# Regulation.net
KiCad netlist of a schematic drawn in Altium Designer
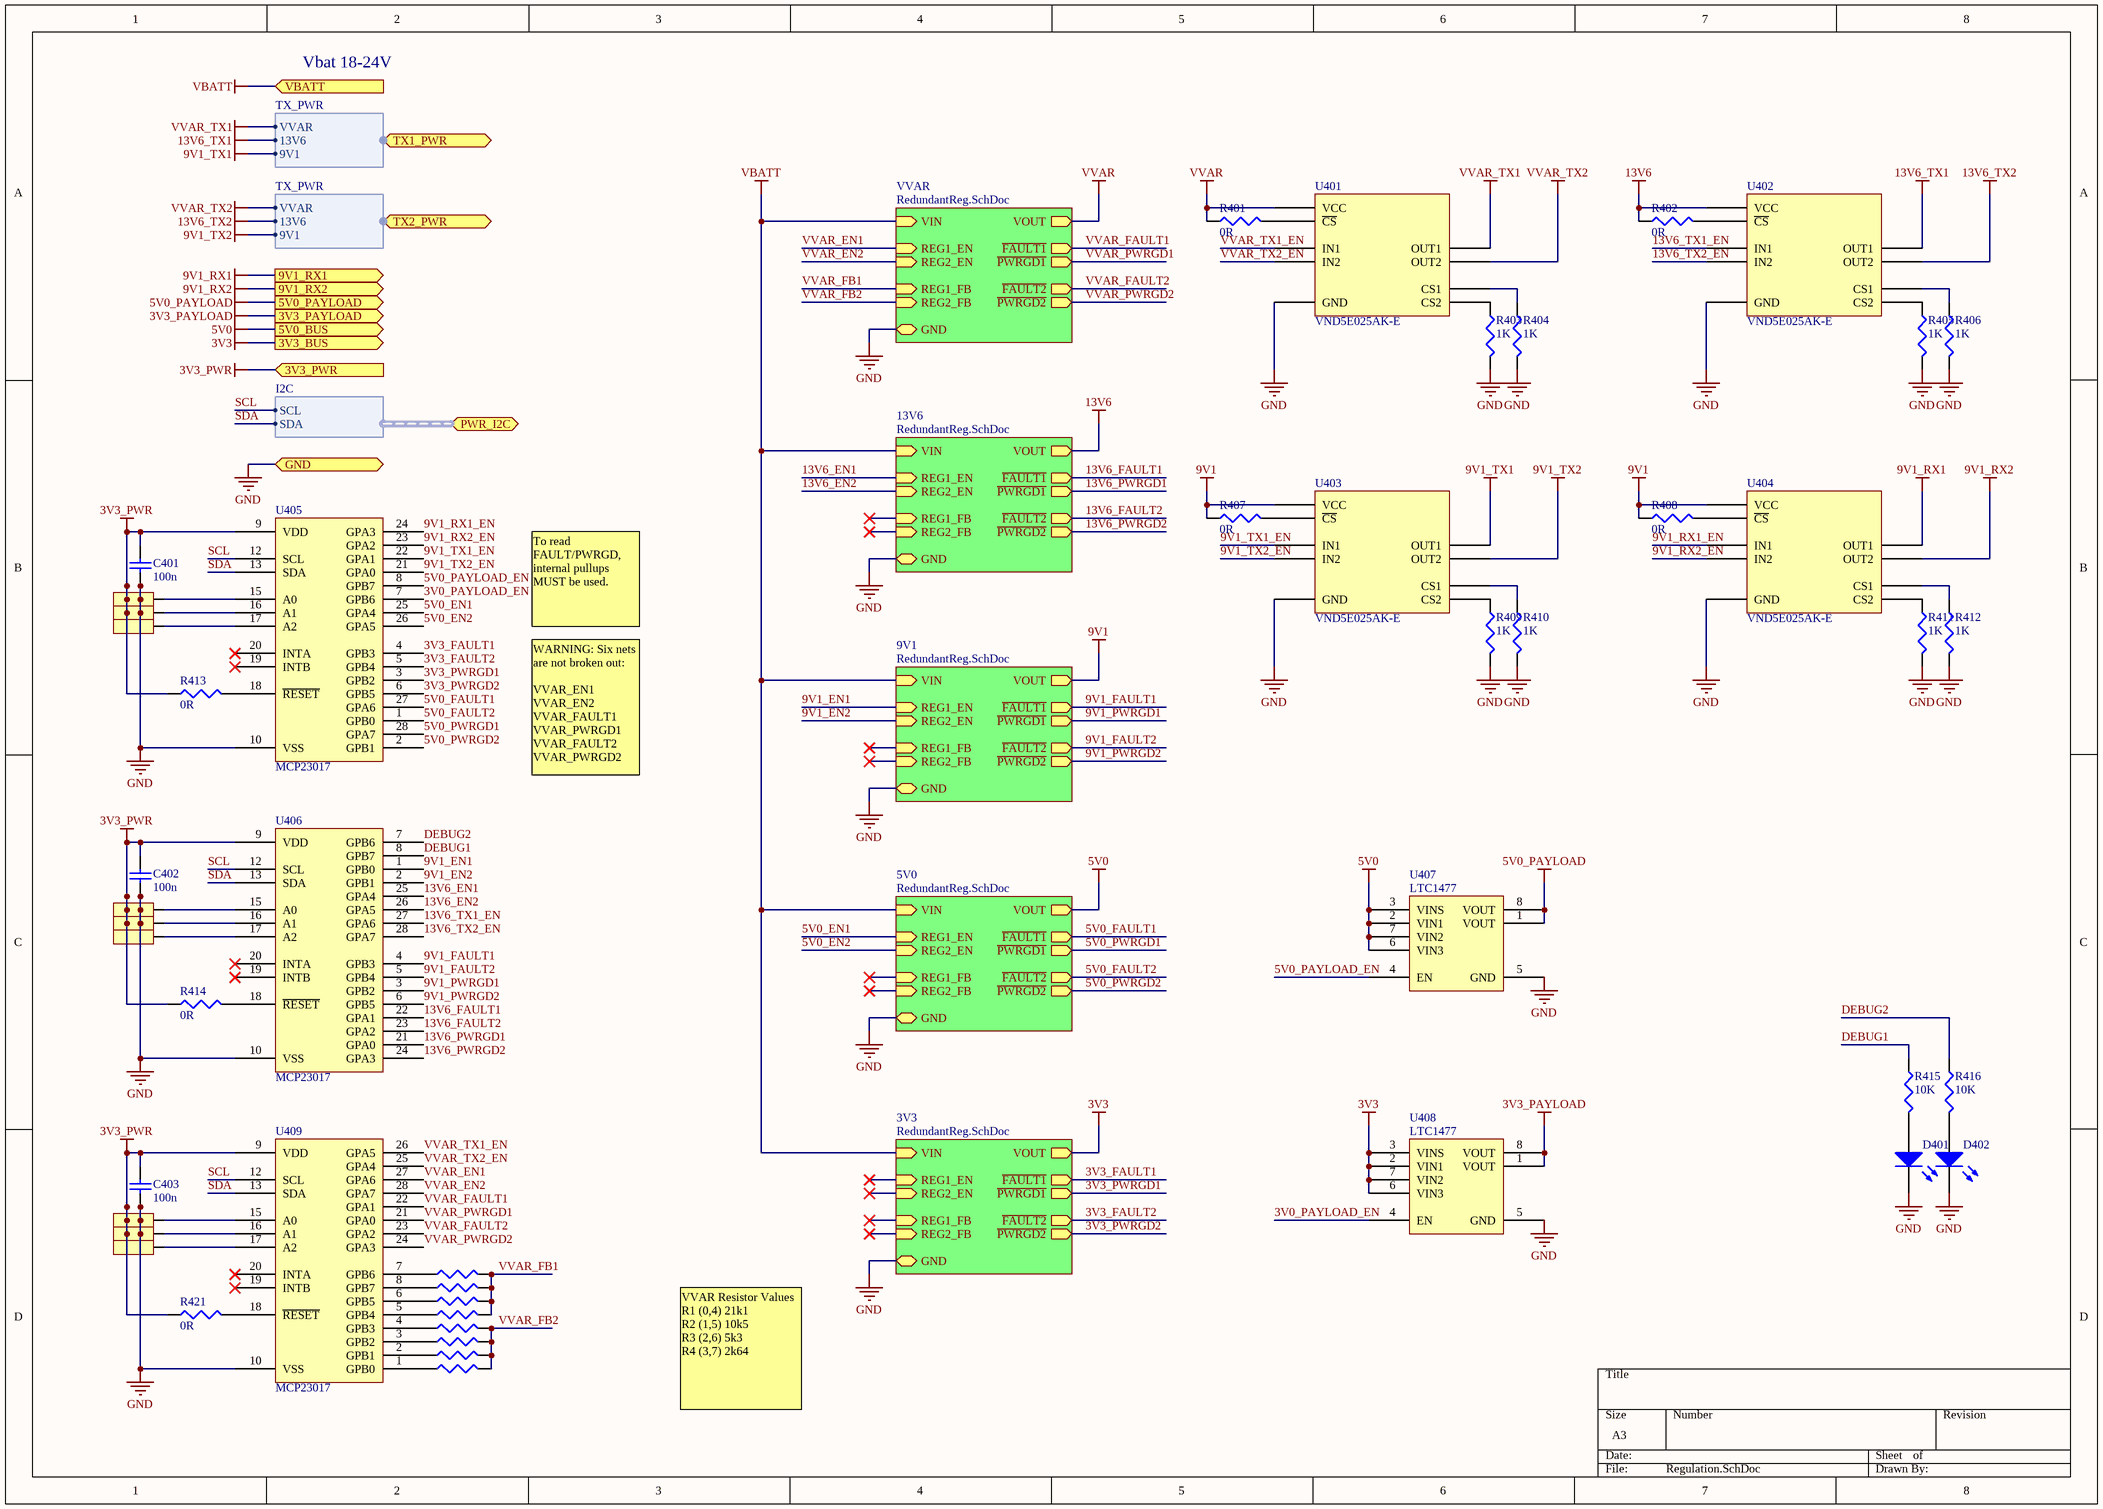
[diagram p0: Regulation.SchDoc]

(export (version "E")
  (design (tool "Eeschema 10.0.6"))
  (components
    (comp (ref "C401")
      (value "100n")
      (footprint "R0805M")
      (description "Capacitor")
      (fields (field (name "PUBLISHER") "Altium Limited"))
      (libsource (lib "Miscellaneous Devices") (part "Cap"))
    )
    (comp (ref "C402")
      (value "100n")
      (footprint "R0805M")
      (description "Capacitor")
      (fields (field (name "PUBLISHER") "Altium Limited"))
      (libsource (lib "Miscellaneous Devices") (part "Cap"))
    )
    (comp (ref "C403")
      (value "100n")
      (footprint "R0805M")
      (description "Capacitor")
      (fields (field (name "PUBLISHER") "Altium Limited"))
      (libsource (lib "Miscellaneous Devices") (part "Cap"))
    )
    (comp (ref "D401")
      (value "LED0")
      (footprint "R0805M")
      (description "Typical INFRARED GaAs LED")
      (fields (field (name "PUBLISHER") "Altium Limited"))
      (libsource (lib "Miscellaneous Devices") (part "LED0"))
    )
    (comp (ref "D402")
      (value "LED0")
      (footprint "R0805M")
      (description "Typical INFRARED GaAs LED")
      (fields (field (name "PUBLISHER") "Altium Limited"))
      (libsource (lib "Miscellaneous Devices") (part "LED0"))
    )
    (comp (ref "J401")
      (value "3-WAY JUMPER")
      (footprint "J1205M")
      (libsource (lib "SchLib") (part "3-WAY JUMPER"))
    )
    (comp (ref "J402")
      (value "3-WAY JUMPER")
      (footprint "J1205M")
      (libsource (lib "SchLib") (part "3-WAY JUMPER"))
    )
    (comp (ref "J403")
      (value "3-WAY JUMPER")
      (footprint "J1205M")
      (libsource (lib "SchLib") (part "3-WAY JUMPER"))
    )
    (comp (ref "J404")
      (value "3-WAY JUMPER")
      (footprint "J1205M")
      (libsource (lib "SchLib") (part "3-WAY JUMPER"))
    )
    (comp (ref "J405")
      (value "3-WAY JUMPER")
      (footprint "J1205M")
      (libsource (lib "SchLib") (part "3-WAY JUMPER"))
    )
    (comp (ref "J406")
      (value "3-WAY JUMPER")
      (footprint "J1205M")
      (libsource (lib "SchLib") (part "3-WAY JUMPER"))
    )
    (comp (ref "J407")
      (value "3-WAY JUMPER")
      (footprint "J1205M")
      (libsource (lib "SchLib") (part "3-WAY JUMPER"))
    )
    (comp (ref "J408")
      (value "3-WAY JUMPER")
      (footprint "J1205M")
      (libsource (lib "SchLib") (part "3-WAY JUMPER"))
    )
    (comp (ref "J409")
      (value "3-WAY JUMPER")
      (footprint "J1205M")
      (libsource (lib "SchLib") (part "3-WAY JUMPER"))
    )
    (comp (ref "R401")
      (value "0R")
      (footprint "R0402M")
      (description "Resistor")
      (fields (field (name "PUBLISHER") "Altium Limited"))
      (libsource (lib "Miscellaneous Devices") (part "Res3"))
    )
    (comp (ref "R402")
      (value "0R")
      (footprint "R0402M")
      (description "Resistor")
      (fields (field (name "PUBLISHER") "Altium Limited"))
      (libsource (lib "Miscellaneous Devices") (part "Res3"))
    )
    (comp (ref "R403")
      (value "1K")
      (footprint "R0402M")
      (description "Resistor")
      (fields (field (name "PUBLISHER") "Altium Limited"))
      (libsource (lib "Miscellaneous Devices") (part "Res3"))
    )
    (comp (ref "R404")
      (value "1K")
      (footprint "R0402M")
      (description "Resistor")
      (fields (field (name "PUBLISHER") "Altium Limited"))
      (libsource (lib "Miscellaneous Devices") (part "Res3"))
    )
    (comp (ref "R405")
      (value "1K")
      (footprint "R0402M")
      (description "Resistor")
      (fields (field (name "PUBLISHER") "Altium Limited"))
      (libsource (lib "Miscellaneous Devices") (part "Res3"))
    )
    (comp (ref "R406")
      (value "1K")
      (footprint "R0402M")
      (description "Resistor")
      (fields (field (name "PUBLISHER") "Altium Limited"))
      (libsource (lib "Miscellaneous Devices") (part "Res3"))
    )
    (comp (ref "R407")
      (value "0R")
      (footprint "R0402M")
      (description "Resistor")
      (fields (field (name "PUBLISHER") "Altium Limited"))
      (libsource (lib "Miscellaneous Devices") (part "Res3"))
    )
    (comp (ref "R408")
      (value "0R")
      (footprint "R0402M")
      (description "Resistor")
      (fields (field (name "PUBLISHER") "Altium Limited"))
      (libsource (lib "Miscellaneous Devices") (part "Res3"))
    )
    (comp (ref "R409")
      (value "1K")
      (footprint "R0402M")
      (description "Resistor")
      (fields (field (name "PUBLISHER") "Altium Limited"))
      (libsource (lib "Miscellaneous Devices") (part "Res3"))
    )
    (comp (ref "R410")
      (value "1K")
      (footprint "R0402M")
      (description "Resistor")
      (fields (field (name "PUBLISHER") "Altium Limited"))
      (libsource (lib "Miscellaneous Devices") (part "Res3"))
    )
    (comp (ref "R411")
      (value "1K")
      (footprint "R0402M")
      (description "Resistor")
      (fields (field (name "PUBLISHER") "Altium Limited"))
      (libsource (lib "Miscellaneous Devices") (part "Res3"))
    )
    (comp (ref "R412")
      (value "1K")
      (footprint "R0402M")
      (description "Resistor")
      (fields (field (name "PUBLISHER") "Altium Limited"))
      (libsource (lib "Miscellaneous Devices") (part "Res3"))
    )
    (comp (ref "R413")
      (value "0R")
      (footprint "R0402M")
      (description "Resistor")
      (fields (field (name "PUBLISHER") "Altium Limited"))
      (libsource (lib "Miscellaneous Devices") (part "Res3"))
    )
    (comp (ref "R414")
      (value "0R")
      (footprint "R0402M")
      (description "Resistor")
      (fields (field (name "PUBLISHER") "Altium Limited"))
      (libsource (lib "Miscellaneous Devices") (part "Res3"))
    )
    (comp (ref "R415")
      (value "10K")
      (footprint "R0402M")
      (description "Resistor")
      (fields (field (name "PUBLISHER") "Altium Limited"))
      (libsource (lib "Miscellaneous Devices") (part "Res3"))
    )
    (comp (ref "R416")
      (value "10K")
      (footprint "R0402M")
      (description "Resistor")
      (fields (field (name "PUBLISHER") "Altium Limited"))
      (libsource (lib "Miscellaneous Devices") (part "Res3"))
    )
    (comp (ref "R417")
      (value "VSET_1")
      (footprint "R0805M")
      (description "Resistor")
      (fields (field (name "PUBLISHER") "Altium Limited"))
      (libsource (lib "Miscellaneous Devices") (part "Res3"))
    )
    (comp (ref "R418")
      (value "VSET_1")
      (footprint "R0805M")
      (description "Resistor")
      (fields (field (name "PUBLISHER") "Altium Limited"))
      (libsource (lib "Miscellaneous Devices") (part "Res3"))
    )
    (comp (ref "R419")
      (value "VSET_1")
      (footprint "R0805M")
      (description "Resistor")
      (fields (field (name "PUBLISHER") "Altium Limited"))
      (libsource (lib "Miscellaneous Devices") (part "Res3"))
    )
    (comp (ref "R420")
      (value "VSET_1")
      (footprint "R0805M")
      (description "Resistor")
      (fields (field (name "PUBLISHER") "Altium Limited"))
      (libsource (lib "Miscellaneous Devices") (part "Res3"))
    )
    (comp (ref "R421")
      (value "0R")
      (footprint "R0402M")
      (description "Resistor")
      (fields (field (name "PUBLISHER") "Altium Limited"))
      (libsource (lib "Miscellaneous Devices") (part "Res3"))
    )
    (comp (ref "R422")
      (value "VSET_1")
      (footprint "R0805M")
      (description "Resistor")
      (fields (field (name "PUBLISHER") "Altium Limited"))
      (libsource (lib "Miscellaneous Devices") (part "Res3"))
    )
    (comp (ref "R423")
      (value "VSET_1")
      (footprint "R0805M")
      (description "Resistor")
      (fields (field (name "PUBLISHER") "Altium Limited"))
      (libsource (lib "Miscellaneous Devices") (part "Res3"))
    )
    (comp (ref "R424")
      (value "VSET_1")
      (footprint "R0805M")
      (description "Resistor")
      (fields (field (name "PUBLISHER") "Altium Limited"))
      (libsource (lib "Miscellaneous Devices") (part "Res3"))
    )
    (comp (ref "R425")
      (value "VSET_1")
      (footprint "R0805M")
      (description "Resistor")
      (fields (field (name "PUBLISHER") "Altium Limited"))
      (libsource (lib "Miscellaneous Devices") (part "Res3"))
    )
    (comp (ref "U401")
      (value "VND5E025AK-E")
      (footprint "SSO24")
      (description "Double channel high-side driver with analog current sense")
      (libsource (lib "SchLib") (part "VND5E025AK-E"))
    )
    (comp (ref "U402")
      (value "VND5E025AK-E")
      (footprint "SSO24")
      (description "Double channel high-side driver with analog current sense")
      (libsource (lib "SchLib") (part "VND5E025AK-E"))
    )
    (comp (ref "U403")
      (value "VND5E025AK-E")
      (footprint "SSO24")
      (description "Double channel high-side driver with analog current sense")
      (libsource (lib "SchLib") (part "VND5E025AK-E"))
    )
    (comp (ref "U404")
      (value "VND5E025AK-E")
      (footprint "SSO24")
      (description "Double channel high-side driver with analog current sense")
      (libsource (lib "SchLib") (part "VND5E025AK-E"))
    )
    (comp (ref "U405")
      (value "MCP23017")
      (footprint "SSOP28")
      (description "16-Bit I/O Expander with Serial Interface")
      (libsource (lib "SchLib") (part "MCP23017"))
    )
    (comp (ref "U406")
      (value "MCP23017")
      (footprint "SSOP28")
      (description "16-Bit I/O Expander with Serial Interface")
      (libsource (lib "") (part "MCP23017_2"))
    )
    (comp (ref "U407")
      (value "LTC1477")
      (footprint "SO8")
      (description "Single Protected High Side Switches")
      (libsource (lib "SchLib") (part "LTC1477"))
    )
    (comp (ref "U408")
      (value "LTC1477")
      (footprint "SO8")
      (description "Single Protected High Side Switches")
      (libsource (lib "SchLib") (part "LTC1477"))
    )
    (comp (ref "U409")
      (value "MCP23017")
      (footprint "SSOP28")
      (description "16-Bit I/O Expander with Serial Interface")
      (libsource (lib "") (part "MCP23017_1"))
    )
  )
  (nets
    (net (code "3") (name "/3V0_PAYLOAD_EN") (class "Default")
      (node (ref "U405") (pin "7") (pinfunction "GPB6_7") (pintype "passive"))
      (node (ref "U408") (pin "4") (pinfunction "EN_4") (pintype "passive"))
    )
    (net (code "4") (name "/3V3_FAULT1") (class "Default")
      (node (ref "U405") (pin "4") (pinfunction "GPB3_4") (pintype "passive"))
    )
    (net (code "5") (name "/3V3_FAULT2") (class "Default")
      (node (ref "U405") (pin "5") (pinfunction "GPB4_5") (pintype "passive"))
    )
    (net (code "6") (name "/3V3_PWRGD1") (class "Default")
      (node (ref "U405") (pin "3") (pinfunction "GPB2_3") (pintype "passive"))
    )
    (net (code "7") (name "/3V3_PWRGD2") (class "Default")
      (node (ref "U405") (pin "6") (pinfunction "GPB5_6") (pintype "passive"))
    )
    (net (code "8") (name "/5V0_EN1") (class "Default")
      (node (ref "U405") (pin "25") (pinfunction "GPA4_25") (pintype "passive"))
    )
    (net (code "9") (name "/5V0_EN2") (class "Default")
      (node (ref "U405") (pin "26") (pinfunction "GPA5_26") (pintype "passive"))
    )
    (net (code "10") (name "/5V0_FAULT1") (class "Default")
      (node (ref "U405") (pin "27") (pinfunction "GPA6_27") (pintype "passive"))
    )
    (net (code "11") (name "/5V0_FAULT2") (class "Default")
      (node (ref "U405") (pin "1") (pinfunction "GPB0_1") (pintype "passive"))
    )
    (net (code "12") (name "/5V0_PAYLOAD_EN") (class "Default")
      (node (ref "U405") (pin "8") (pinfunction "GPB7_8") (pintype "passive"))
      (node (ref "U407") (pin "4") (pinfunction "EN_4") (pintype "passive"))
    )
    (net (code "13") (name "/5V0_PWRGD1") (class "Default")
      (node (ref "U405") (pin "28") (pinfunction "GPA7_28") (pintype "passive"))
    )
    (net (code "14") (name "/5V0_PWRGD2") (class "Default")
      (node (ref "U405") (pin "2") (pinfunction "GPB1_2") (pintype "passive"))
    )
    (net (code "15") (name "/9V1_EN1") (class "Default")
      (node (ref "U406") (pin "1") (pinfunction "GPB0_1") (pintype "passive"))
    )
    (net (code "16") (name "/9V1_EN2") (class "Default")
      (node (ref "U406") (pin "2") (pinfunction "GPB1_2") (pintype "passive"))
    )
    (net (code "17") (name "/9V1_FAULT1") (class "Default")
      (node (ref "U406") (pin "4") (pinfunction "GPB3_4") (pintype "passive"))
    )
    (net (code "18") (name "/9V1_FAULT2") (class "Default")
      (node (ref "U406") (pin "5") (pinfunction "GPB4_5") (pintype "passive"))
    )
    (net (code "19") (name "/9V1_PWRGD1") (class "Default")
      (node (ref "U406") (pin "3") (pinfunction "GPB2_3") (pintype "passive"))
    )
    (net (code "20") (name "/9V1_PWRGD2") (class "Default")
      (node (ref "U406") (pin "6") (pinfunction "GPB5_6") (pintype "passive"))
    )
    (net (code "21") (name "/9V1_RX1_EN") (class "Default")
      (node (ref "U404") (pin "IN1") (pinfunction "IN1_IN1") (pintype "passive"))
      (node (ref "U405") (pin "24") (pinfunction "GPA3_24") (pintype "passive"))
    )
    (net (code "22") (name "/9V1_RX2_EN") (class "Default")
      (node (ref "U404") (pin "IN2") (pinfunction "IN2_IN2") (pintype "passive"))
      (node (ref "U405") (pin "23") (pinfunction "GPA2_23") (pintype "passive"))
    )
    (net (code "23") (name "/9V1_TX1_EN") (class "Default")
      (node (ref "U403") (pin "IN1") (pinfunction "IN1_IN1") (pintype "passive"))
      (node (ref "U405") (pin "22") (pinfunction "GPA1_22") (pintype "passive"))
    )
    (net (code "24") (name "/9V1_TX2_EN") (class "Default")
      (node (ref "U403") (pin "IN2") (pinfunction "IN2_IN2") (pintype "passive"))
      (node (ref "U405") (pin "21") (pinfunction "GPA0_21") (pintype "passive"))
    )
    (net (code "25") (name "/13V6_EN1") (class "Default")
      (node (ref "U406") (pin "25") (pinfunction "GPA4_25") (pintype "passive"))
    )
    (net (code "26") (name "/13V6_EN2") (class "Default")
      (node (ref "U406") (pin "26") (pinfunction "GPA5_26") (pintype "passive"))
    )
    (net (code "27") (name "/13V6_FAULT1") (class "Default")
      (node (ref "U406") (pin "22") (pinfunction "GPA1_22") (pintype "passive"))
    )
    (net (code "28") (name "/13V6_FAULT2") (class "Default")
      (node (ref "U406") (pin "23") (pinfunction "GPA2_23") (pintype "passive"))
    )
    (net (code "29") (name "/13V6_PWRGD1") (class "Default")
      (node (ref "U406") (pin "21") (pinfunction "GPA0_21") (pintype "passive"))
    )
    (net (code "30") (name "/13V6_PWRGD2") (class "Default")
      (node (ref "U406") (pin "24") (pinfunction "GPA3_24") (pintype "passive"))
    )
    (net (code "31") (name "/13V6_TX1_EN") (class "Default")
      (node (ref "U402") (pin "IN1") (pinfunction "IN1_IN1") (pintype "passive"))
      (node (ref "U406") (pin "27") (pinfunction "GPA6_27") (pintype "passive"))
    )
    (net (code "32") (name "/13V6_TX2_EN") (class "Default")
      (node (ref "U402") (pin "IN2") (pinfunction "IN2_IN2") (pintype "passive"))
      (node (ref "U406") (pin "28") (pinfunction "GPA7_28") (pintype "passive"))
    )
    (net (code "33") (name "/DEBUG1") (class "Default")
      (node (ref "R415") (pin "1") (pinfunction "1_1") (pintype "passive"))
      (node (ref "U406") (pin "8") (pinfunction "GPB7_8") (pintype "passive"))
    )
    (net (code "34") (name "/DEBUG2") (class "Default")
      (node (ref "R416") (pin "1") (pinfunction "1_1") (pintype "passive"))
      (node (ref "U406") (pin "7") (pinfunction "GPB6_7") (pintype "passive"))
    )
    (net (code "45") (name "/SCL") (class "Default")
      (node (ref "U405") (pin "12") (pinfunction "SCL_12") (pintype "passive"))
      (node (ref "U406") (pin "12") (pinfunction "SCL_12") (pintype "passive"))
      (node (ref "U409") (pin "12") (pinfunction "SCL_12") (pintype "passive"))
    )
    (net (code "46") (name "/SDA") (class "Default")
      (node (ref "U405") (pin "13") (pinfunction "SDA_13") (pintype "passive"))
      (node (ref "U406") (pin "13") (pinfunction "SDA_13") (pintype "passive"))
      (node (ref "U409") (pin "13") (pinfunction "SDA_13") (pintype "passive"))
    )
    (net (code "47") (name "/VVAR_EN1") (class "Default")
      (node (ref "U409") (pin "27") (pinfunction "GPA6_27") (pintype "passive"))
    )
    (net (code "48") (name "/VVAR_EN2") (class "Default")
      (node (ref "U409") (pin "28") (pinfunction "GPA7_28") (pintype "passive"))
    )
    (net (code "49") (name "/VVAR_FAULT1") (class "Default")
      (node (ref "U409") (pin "22") (pinfunction "GPA1_22") (pintype "passive"))
    )
    (net (code "50") (name "/VVAR_FAULT2") (class "Default")
      (node (ref "U409") (pin "23") (pinfunction "GPA2_23") (pintype "passive"))
    )
    (net (code "51") (name "/VVAR_FB1") (class "Default")
      (node (ref "R417") (pin "2") (pinfunction "2_2") (pintype "passive"))
      (node (ref "R418") (pin "2") (pinfunction "2_2") (pintype "passive"))
      (node (ref "R419") (pin "2") (pinfunction "2_2") (pintype "passive"))
      (node (ref "R420") (pin "2") (pinfunction "2_2") (pintype "passive"))
    )
    (net (code "52") (name "/VVAR_FB2") (class "Default")
      (node (ref "R422") (pin "2") (pinfunction "2_2") (pintype "passive"))
      (node (ref "R423") (pin "2") (pinfunction "2_2") (pintype "passive"))
      (node (ref "R424") (pin "2") (pinfunction "2_2") (pintype "passive"))
      (node (ref "R425") (pin "2") (pinfunction "2_2") (pintype "passive"))
    )
    (net (code "53") (name "/VVAR_PWRGD1") (class "Default")
      (node (ref "U409") (pin "21") (pinfunction "GPA0_21") (pintype "passive"))
    )
    (net (code "54") (name "/VVAR_PWRGD2") (class "Default")
      (node (ref "U409") (pin "24") (pinfunction "GPA3_24") (pintype "passive"))
    )
    (net (code "55") (name "/VVAR_TX1_EN") (class "Default")
      (node (ref "U401") (pin "IN1") (pinfunction "IN1_IN1") (pintype "passive"))
      (node (ref "U409") (pin "26") (pinfunction "GPA5_26") (pintype "passive"))
    )
    (net (code "56") (name "/VVAR_TX2_EN") (class "Default")
      (node (ref "U401") (pin "IN2") (pinfunction "IN2_IN2") (pintype "passive"))
      (node (ref "U409") (pin "25") (pinfunction "GPA4_25") (pintype "passive"))
    )
    (net (code "59") (name "3V3") (class "Default")
      (node (ref "U408") (pin "2") (pinfunction "VIN1_2") (pintype "passive"))
      (node (ref "U408") (pin "3") (pinfunction "VINS_3") (pintype "passive"))
      (node (ref "U408") (pin "6") (pinfunction "VIN3_6") (pintype "passive"))
      (node (ref "U408") (pin "7") (pinfunction "VIN2_7") (pintype "passive"))
    )
    (net (code "60") (name "3V3_PAYLOAD") (class "Default")
      (node (ref "U408") (pin "1") (pinfunction "VOUT_1") (pintype "passive"))
      (node (ref "U408") (pin "8") (pinfunction "VOUT_8") (pintype "passive"))
    )
    (net (code "61") (name "3V3_PWR") (class "Default")
      (node (ref "C401") (pin "1") (pinfunction "1_1") (pintype "passive"))
      (node (ref "C402") (pin "1") (pinfunction "1_1") (pintype "passive"))
      (node (ref "C403") (pin "1") (pinfunction "1_1") (pintype "passive"))
      (node (ref "J401") (pin "1") (pintype "passive"))
      (node (ref "J402") (pin "1") (pintype "passive"))
      (node (ref "J403") (pin "1") (pintype "passive"))
      (node (ref "J404") (pin "1") (pintype "passive"))
      (node (ref "J405") (pin "1") (pintype "passive"))
      (node (ref "J406") (pin "1") (pintype "passive"))
      (node (ref "J407") (pin "1") (pintype "passive"))
      (node (ref "J408") (pin "1") (pintype "passive"))
      (node (ref "J409") (pin "1") (pintype "passive"))
      (node (ref "R413") (pin "1") (pinfunction "1_1") (pintype "passive"))
      (node (ref "R414") (pin "1") (pinfunction "1_1") (pintype "passive"))
      (node (ref "R421") (pin "1") (pinfunction "1_1") (pintype "passive"))
      (node (ref "U405") (pin "9") (pinfunction "VDD_9") (pintype "passive"))
      (node (ref "U406") (pin "9") (pinfunction "VDD_9") (pintype "passive"))
      (node (ref "U409") (pin "9") (pinfunction "VDD_9") (pintype "passive"))
    )
    (net (code "62") (name "5V0") (class "Default")
      (node (ref "U407") (pin "2") (pinfunction "VIN1_2") (pintype "passive"))
      (node (ref "U407") (pin "3") (pinfunction "VINS_3") (pintype "passive"))
      (node (ref "U407") (pin "6") (pinfunction "VIN3_6") (pintype "passive"))
      (node (ref "U407") (pin "7") (pinfunction "VIN2_7") (pintype "passive"))
    )
    (net (code "63") (name "5V0_PAYLOAD") (class "Default")
      (node (ref "U407") (pin "1") (pinfunction "VOUT_1") (pintype "passive"))
      (node (ref "U407") (pin "8") (pinfunction "VOUT_8") (pintype "passive"))
    )
    (net (code "64") (name "9V1") (class "Default")
      (node (ref "R407") (pin "1") (pinfunction "1_1") (pintype "passive"))
      (node (ref "R408") (pin "1") (pinfunction "1_1") (pintype "passive"))
      (node (ref "U403") (pin "VCC") (pinfunction "VCC_VCC") (pintype "passive"))
      (node (ref "U404") (pin "VCC") (pinfunction "VCC_VCC") (pintype "passive"))
    )
    (net (code "65") (name "9V1_RX1") (class "Default")
      (node (ref "U404") (pin "OUT1") (pinfunction "OUT1_OUT1") (pintype "passive"))
    )
    (net (code "66") (name "9V1_RX2") (class "Default")
      (node (ref "U404") (pin "OUT2") (pinfunction "OUT2_OUT2") (pintype "passive"))
    )
    (net (code "67") (name "9V1_TX1") (class "Default")
      (node (ref "U403") (pin "OUT1") (pinfunction "OUT1_OUT1") (pintype "passive"))
    )
    (net (code "68") (name "9V1_TX2") (class "Default")
      (node (ref "U403") (pin "OUT2") (pinfunction "OUT2_OUT2") (pintype "passive"))
    )
    (net (code "69") (name "13V6") (class "Default")
      (node (ref "R402") (pin "1") (pinfunction "1_1") (pintype "passive"))
      (node (ref "U402") (pin "VCC") (pinfunction "VCC_VCC") (pintype "passive"))
    )
    (net (code "70") (name "13V6_TX1") (class "Default")
      (node (ref "U402") (pin "OUT1") (pinfunction "OUT1_OUT1") (pintype "passive"))
    )
    (net (code "71") (name "13V6_TX2") (class "Default")
      (node (ref "U402") (pin "OUT2") (pinfunction "OUT2_OUT2") (pintype "passive"))
    )
    (net (code "72") (name "GND") (class "Default")
      (node (ref "C401") (pin "2") (pinfunction "2_2") (pintype "passive"))
      (node (ref "C402") (pin "2") (pinfunction "2_2") (pintype "passive"))
      (node (ref "C403") (pin "2") (pinfunction "2_2") (pintype "passive"))
      (node (ref "D401") (pin "2") (pinfunction "K_2") (pintype "passive"))
      (node (ref "D402") (pin "2") (pinfunction "K_2") (pintype "passive"))
      (node (ref "J401") (pin "3") (pintype "passive"))
      (node (ref "J402") (pin "3") (pintype "passive"))
      (node (ref "J403") (pin "3") (pintype "passive"))
      (node (ref "J404") (pin "3") (pintype "passive"))
      (node (ref "J405") (pin "3") (pintype "passive"))
      (node (ref "J406") (pin "3") (pintype "passive"))
      (node (ref "J407") (pin "3") (pintype "passive"))
      (node (ref "J408") (pin "3") (pintype "passive"))
      (node (ref "J409") (pin "3") (pintype "passive"))
      (node (ref "R403") (pin "2") (pinfunction "2_2") (pintype "passive"))
      (node (ref "R404") (pin "2") (pinfunction "2_2") (pintype "passive"))
      (node (ref "R405") (pin "2") (pinfunction "2_2") (pintype "passive"))
      (node (ref "R406") (pin "2") (pinfunction "2_2") (pintype "passive"))
      (node (ref "R409") (pin "2") (pinfunction "2_2") (pintype "passive"))
      (node (ref "R410") (pin "2") (pinfunction "2_2") (pintype "passive"))
      (node (ref "R411") (pin "2") (pinfunction "2_2") (pintype "passive"))
      (node (ref "R412") (pin "2") (pinfunction "2_2") (pintype "passive"))
      (node (ref "U401") (pin "GND") (pinfunction "GND_GND") (pintype "passive"))
      (node (ref "U402") (pin "GND") (pinfunction "GND_GND") (pintype "passive"))
      (node (ref "U403") (pin "GND") (pinfunction "GND_GND") (pintype "passive"))
      (node (ref "U404") (pin "GND") (pinfunction "GND_GND") (pintype "passive"))
      (node (ref "U405") (pin "10") (pinfunction "VSS_10") (pintype "passive"))
      (node (ref "U406") (pin "10") (pinfunction "VSS_10") (pintype "passive"))
      (node (ref "U407") (pin "5") (pinfunction "GND_5") (pintype "passive"))
      (node (ref "U408") (pin "5") (pinfunction "GND_5") (pintype "passive"))
      (node (ref "U409") (pin "10") (pinfunction "VSS_10") (pintype "passive"))
    )
    (net (code "73") (name "Net-(D401-A)") (class "Default")
      (node (ref "D401") (pin "1") (pinfunction "A_1") (pintype "passive"))
      (node (ref "R415") (pin "2") (pinfunction "2_2") (pintype "passive"))
    )
    (net (code "74") (name "Net-(D402-A)") (class "Default")
      (node (ref "D402") (pin "1") (pinfunction "A_1") (pintype "passive"))
      (node (ref "R416") (pin "2") (pinfunction "2_2") (pintype "passive"))
    )
    (net (code "75") (name "Net-(R403-Pad1)") (class "Default")
      (node (ref "R403") (pin "1") (pinfunction "1_1") (pintype "passive"))
      (node (ref "U401") (pin "CS2") (pinfunction "CS2_CS2") (pintype "passive"))
    )
    (net (code "76") (name "Net-(R404-Pad1)") (class "Default")
      (node (ref "R404") (pin "1") (pinfunction "1_1") (pintype "passive"))
      (node (ref "U401") (pin "CS1") (pinfunction "CS1_CS1") (pintype "passive"))
    )
    (net (code "77") (name "Net-(R405-Pad1)") (class "Default")
      (node (ref "R405") (pin "1") (pinfunction "1_1") (pintype "passive"))
      (node (ref "U402") (pin "CS2") (pinfunction "CS2_CS2") (pintype "passive"))
    )
    (net (code "78") (name "Net-(R406-Pad1)") (class "Default")
      (node (ref "R406") (pin "1") (pinfunction "1_1") (pintype "passive"))
      (node (ref "U402") (pin "CS1") (pinfunction "CS1_CS1") (pintype "passive"))
    )
    (net (code "79") (name "Net-(R409-Pad1)") (class "Default")
      (node (ref "R409") (pin "1") (pinfunction "1_1") (pintype "passive"))
      (node (ref "U403") (pin "CS2") (pinfunction "CS2_CS2") (pintype "passive"))
    )
    (net (code "80") (name "Net-(R410-Pad1)") (class "Default")
      (node (ref "R410") (pin "1") (pinfunction "1_1") (pintype "passive"))
      (node (ref "U403") (pin "CS1") (pinfunction "CS1_CS1") (pintype "passive"))
    )
    (net (code "81") (name "Net-(R411-Pad1)") (class "Default")
      (node (ref "R411") (pin "1") (pinfunction "1_1") (pintype "passive"))
      (node (ref "U404") (pin "CS2") (pinfunction "CS2_CS2") (pintype "passive"))
    )
    (net (code "82") (name "Net-(R412-Pad1)") (class "Default")
      (node (ref "R412") (pin "1") (pinfunction "1_1") (pintype "passive"))
      (node (ref "U404") (pin "CS1") (pinfunction "CS1_CS1") (pintype "passive"))
    )
    (net (code "83") (name "Net-(U401-~{CS})") (class "Default")
      (node (ref "R401") (pin "2") (pinfunction "2_2") (pintype "passive"))
      (node (ref "U401") (pin "CS_DIS") (pinfunction "~{CS}_CS_DIS") (pintype "passive"))
    )
    (net (code "84") (name "Net-(U402-~{CS})") (class "Default")
      (node (ref "R402") (pin "2") (pinfunction "2_2") (pintype "passive"))
      (node (ref "U402") (pin "CS_DIS") (pinfunction "~{CS}_CS_DIS") (pintype "passive"))
    )
    (net (code "85") (name "Net-(U403-~{CS})") (class "Default")
      (node (ref "R407") (pin "2") (pinfunction "2_2") (pintype "passive"))
      (node (ref "U403") (pin "CS_DIS") (pinfunction "~{CS}_CS_DIS") (pintype "passive"))
    )
    (net (code "86") (name "Net-(U404-~{CS})") (class "Default")
      (node (ref "R408") (pin "2") (pinfunction "2_2") (pintype "passive"))
      (node (ref "U404") (pin "CS_DIS") (pinfunction "~{CS}_CS_DIS") (pintype "passive"))
    )
    (net (code "87") (name "Net-(U405-A0)") (class "Default")
      (node (ref "J401") (pin "2") (pintype "passive"))
      (node (ref "U405") (pin "15") (pinfunction "A0_15") (pintype "passive"))
    )
    (net (code "88") (name "Net-(U405-A1)") (class "Default")
      (node (ref "J402") (pin "2") (pintype "passive"))
      (node (ref "U405") (pin "16") (pinfunction "A1_16") (pintype "passive"))
    )
    (net (code "89") (name "Net-(U405-A2)") (class "Default")
      (node (ref "J403") (pin "2") (pintype "passive"))
      (node (ref "U405") (pin "17") (pinfunction "A2_17") (pintype "passive"))
    )
    (net (code "90") (name "Net-(U405-~{RESET})") (class "Default")
      (node (ref "R413") (pin "2") (pinfunction "2_2") (pintype "passive"))
      (node (ref "U405") (pin "18") (pinfunction "~{RESET}_18") (pintype "passive"))
    )
    (net (code "91") (name "Net-(U406-A0)") (class "Default")
      (node (ref "J404") (pin "2") (pintype "passive"))
      (node (ref "U406") (pin "15") (pinfunction "A0_15") (pintype "passive"))
    )
    (net (code "92") (name "Net-(U406-A1)") (class "Default")
      (node (ref "J405") (pin "2") (pintype "passive"))
      (node (ref "U406") (pin "16") (pinfunction "A1_16") (pintype "passive"))
    )
    (net (code "93") (name "Net-(U406-A2)") (class "Default")
      (node (ref "J406") (pin "2") (pintype "passive"))
      (node (ref "U406") (pin "17") (pinfunction "A2_17") (pintype "passive"))
    )
    (net (code "94") (name "Net-(U406-~{RESET})") (class "Default")
      (node (ref "R414") (pin "2") (pinfunction "2_2") (pintype "passive"))
      (node (ref "U406") (pin "18") (pinfunction "~{RESET}_18") (pintype "passive"))
    )
    (net (code "95") (name "Net-(U409-A0)") (class "Default")
      (node (ref "J407") (pin "2") (pintype "passive"))
      (node (ref "U409") (pin "15") (pinfunction "A0_15") (pintype "passive"))
    )
    (net (code "96") (name "Net-(U409-A1)") (class "Default")
      (node (ref "J408") (pin "2") (pintype "passive"))
      (node (ref "U409") (pin "16") (pinfunction "A1_16") (pintype "passive"))
    )
    (net (code "97") (name "Net-(U409-A2)") (class "Default")
      (node (ref "J409") (pin "2") (pintype "passive"))
      (node (ref "U409") (pin "17") (pinfunction "A2_17") (pintype "passive"))
    )
    (net (code "98") (name "Net-(U409-GPB0)") (class "Default")
      (node (ref "R425") (pin "1") (pinfunction "1_1") (pintype "passive"))
      (node (ref "U409") (pin "1") (pinfunction "GPB0_1") (pintype "passive"))
    )
    (net (code "99") (name "Net-(U409-GPB1)") (class "Default")
      (node (ref "R424") (pin "1") (pinfunction "1_1") (pintype "passive"))
      (node (ref "U409") (pin "2") (pinfunction "GPB1_2") (pintype "passive"))
    )
    (net (code "100") (name "Net-(U409-GPB2)") (class "Default")
      (node (ref "R423") (pin "1") (pinfunction "1_1") (pintype "passive"))
      (node (ref "U409") (pin "3") (pinfunction "GPB2_3") (pintype "passive"))
    )
    (net (code "101") (name "Net-(U409-GPB3)") (class "Default")
      (node (ref "R422") (pin "1") (pinfunction "1_1") (pintype "passive"))
      (node (ref "U409") (pin "4") (pinfunction "GPB3_4") (pintype "passive"))
    )
    (net (code "102") (name "Net-(U409-GPB4)") (class "Default")
      (node (ref "R420") (pin "1") (pinfunction "1_1") (pintype "passive"))
      (node (ref "U409") (pin "5") (pinfunction "GPB4_5") (pintype "passive"))
    )
    (net (code "103") (name "Net-(U409-GPB5)") (class "Default")
      (node (ref "R419") (pin "1") (pinfunction "1_1") (pintype "passive"))
      (node (ref "U409") (pin "6") (pinfunction "GPB5_6") (pintype "passive"))
    )
    (net (code "104") (name "Net-(U409-GPB6)") (class "Default")
      (node (ref "R417") (pin "1") (pinfunction "1_1") (pintype "passive"))
      (node (ref "U409") (pin "7") (pinfunction "GPB6_7") (pintype "passive"))
    )
    (net (code "105") (name "Net-(U409-GPB7)") (class "Default")
      (node (ref "R418") (pin "1") (pinfunction "1_1") (pintype "passive"))
      (node (ref "U409") (pin "8") (pinfunction "GPB7_8") (pintype "passive"))
    )
    (net (code "106") (name "Net-(U409-~{RESET})") (class "Default")
      (node (ref "R421") (pin "2") (pinfunction "2_2") (pintype "passive"))
      (node (ref "U409") (pin "18") (pinfunction "~{RESET}_18") (pintype "passive"))
    )
    (net (code "108") (name "VVAR") (class "Default")
      (node (ref "R401") (pin "1") (pinfunction "1_1") (pintype "passive"))
      (node (ref "U401") (pin "VCC") (pinfunction "VCC_VCC") (pintype "passive"))
    )
    (net (code "109") (name "VVAR_TX1") (class "Default")
      (node (ref "U401") (pin "OUT1") (pinfunction "OUT1_OUT1") (pintype "passive"))
    )
    (net (code "110") (name "VVAR_TX2") (class "Default")
      (node (ref "U401") (pin "OUT2") (pinfunction "OUT2_OUT2") (pintype "passive"))
    )
    (net (code "111") (name "unconnected-(U405-INTA-Pad20)") (class "Default")
      (node (ref "U405") (pin "20") (pinfunction "INTA_20") (pintype "passive+no_connect"))
    )
    (net (code "112") (name "unconnected-(U405-INTB-Pad19)") (class "Default")
      (node (ref "U405") (pin "19") (pinfunction "INTB_19") (pintype "passive+no_connect"))
    )
    (net (code "113") (name "unconnected-(U406-INTA-Pad20)") (class "Default")
      (node (ref "U406") (pin "20") (pinfunction "INTA_20") (pintype "passive+no_connect"))
    )
    (net (code "114") (name "unconnected-(U406-INTB-Pad19)") (class "Default")
      (node (ref "U406") (pin "19") (pinfunction "INTB_19") (pintype "passive+no_connect"))
    )
    (net (code "115") (name "unconnected-(U409-INTA-Pad20)") (class "Default")
      (node (ref "U409") (pin "20") (pinfunction "INTA_20") (pintype "passive+no_connect"))
    )
    (net (code "116") (name "unconnected-(U409-INTB-Pad19)") (class "Default")
      (node (ref "U409") (pin "19") (pinfunction "INTB_19") (pintype "passive+no_connect"))
    )
  )
)
